# RACK32.net
KiCad netlist of a schematic drawn in EAGLE
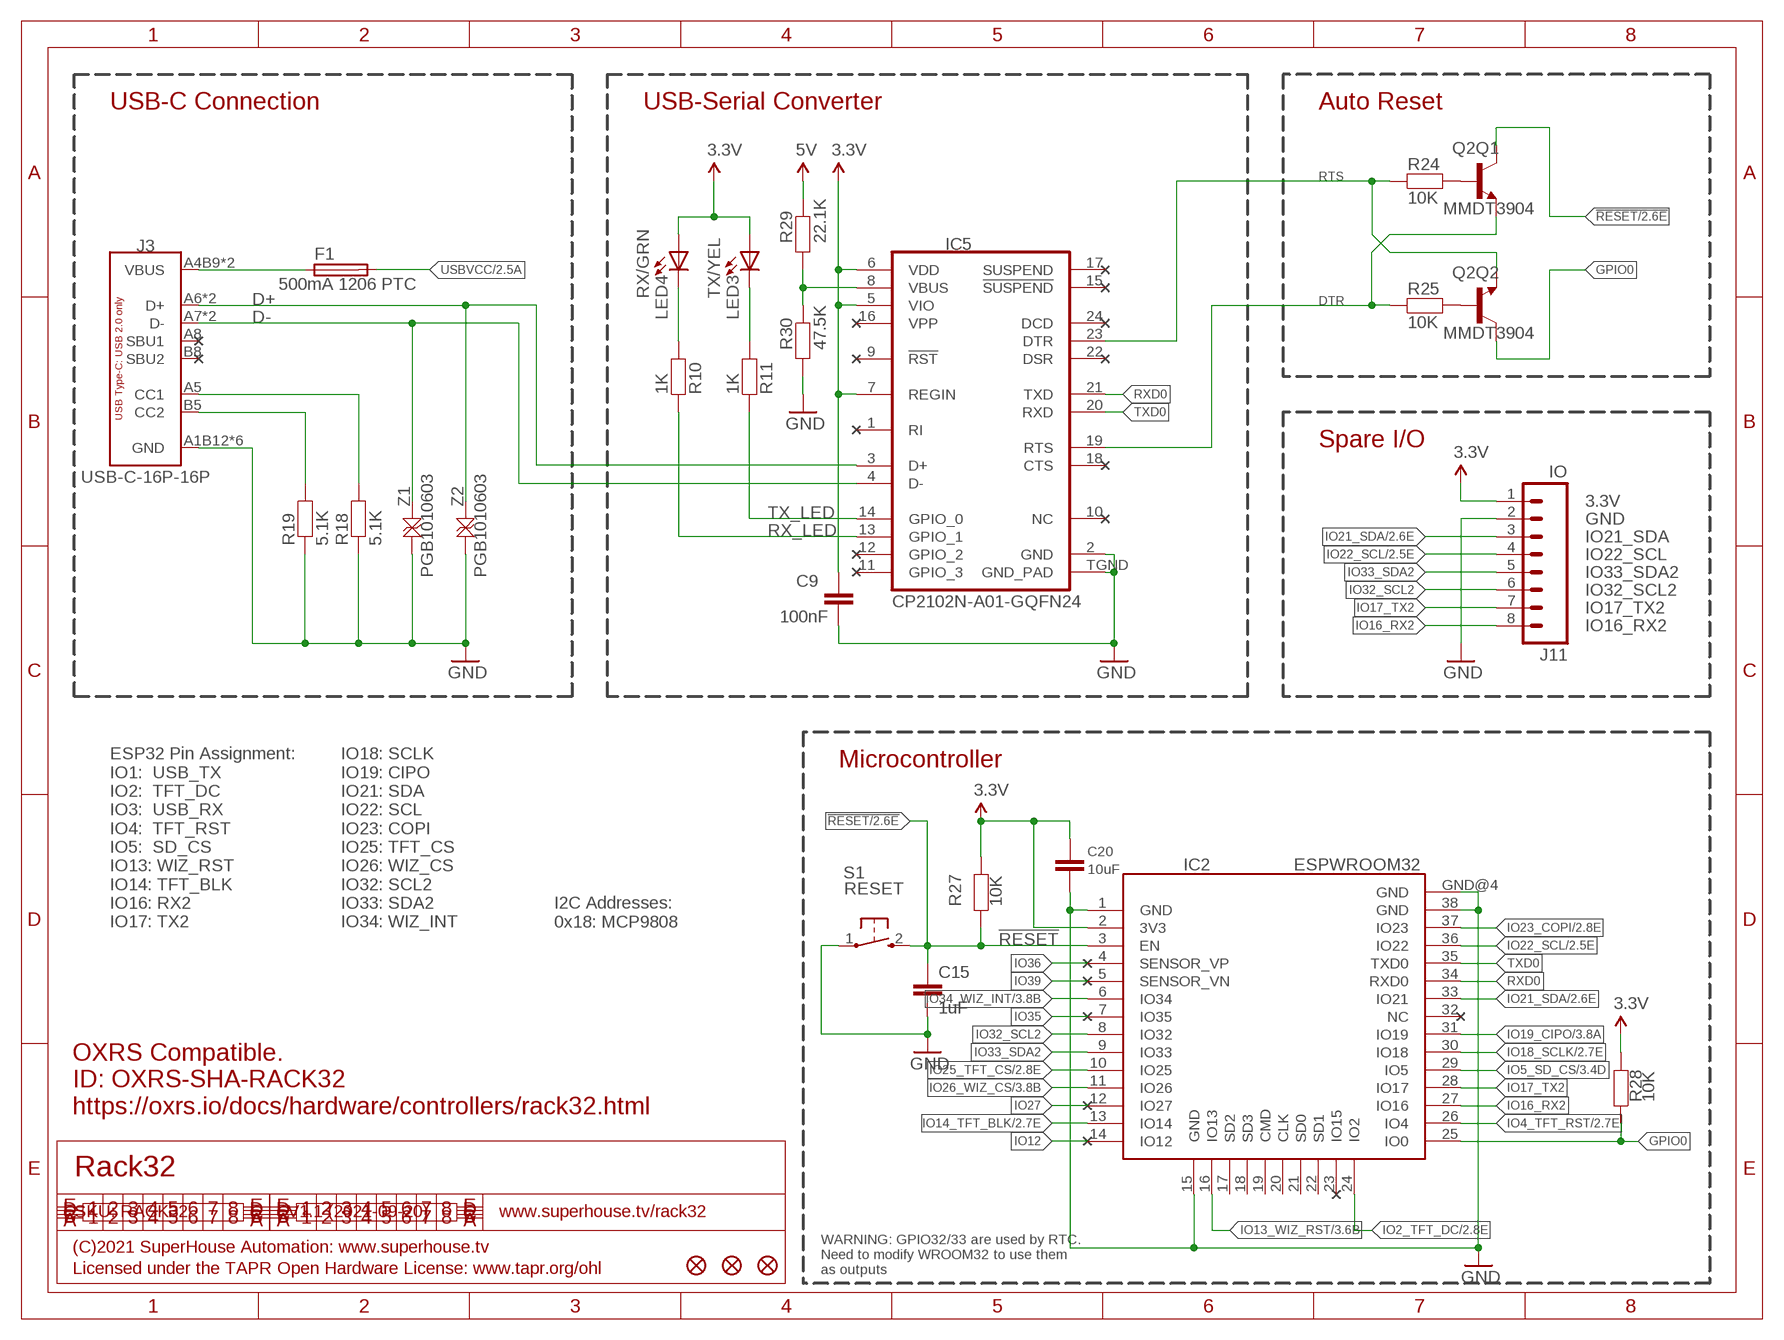
[diagram p0: schematic, sheet 1]
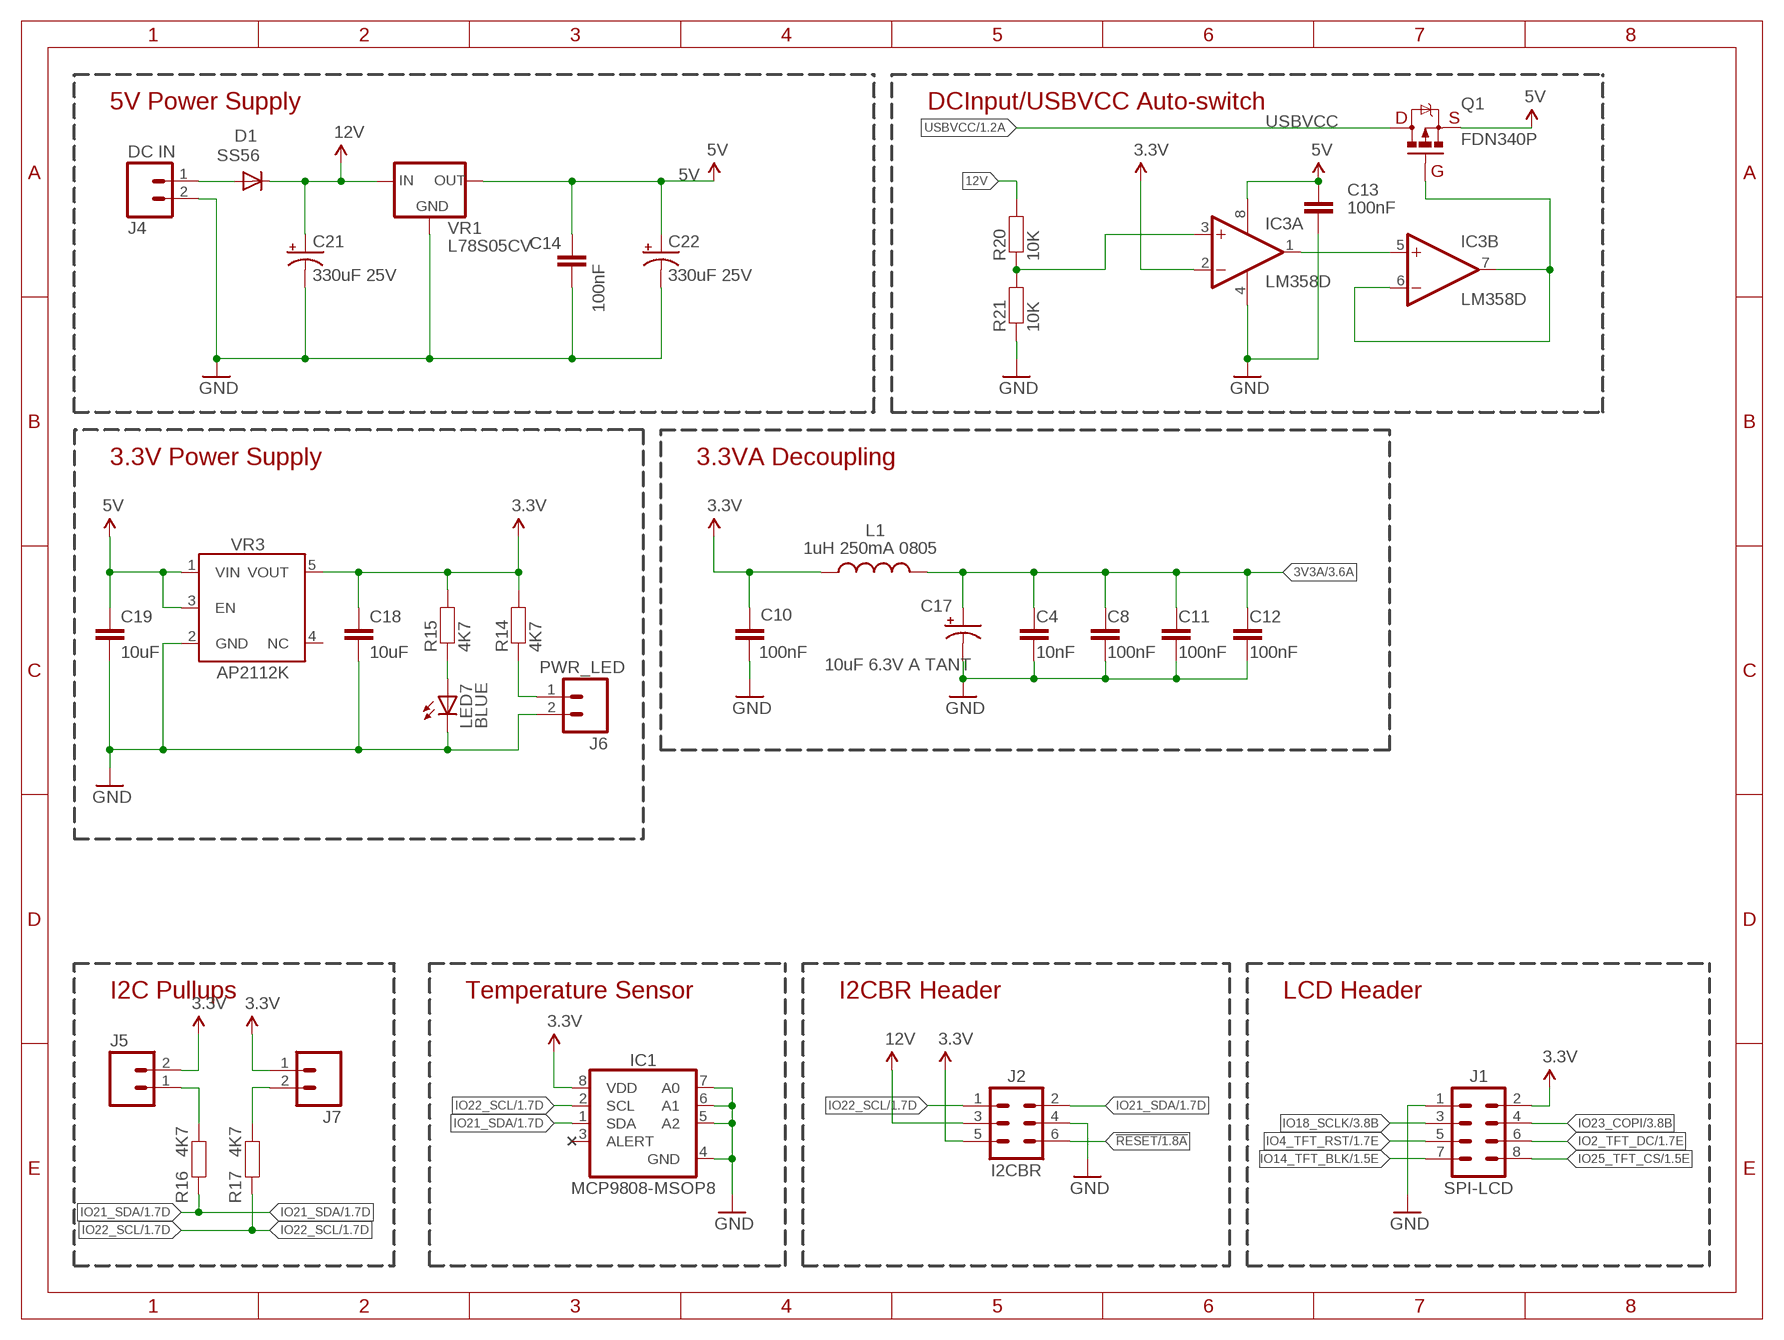
[diagram p1: schematic, sheet 2]
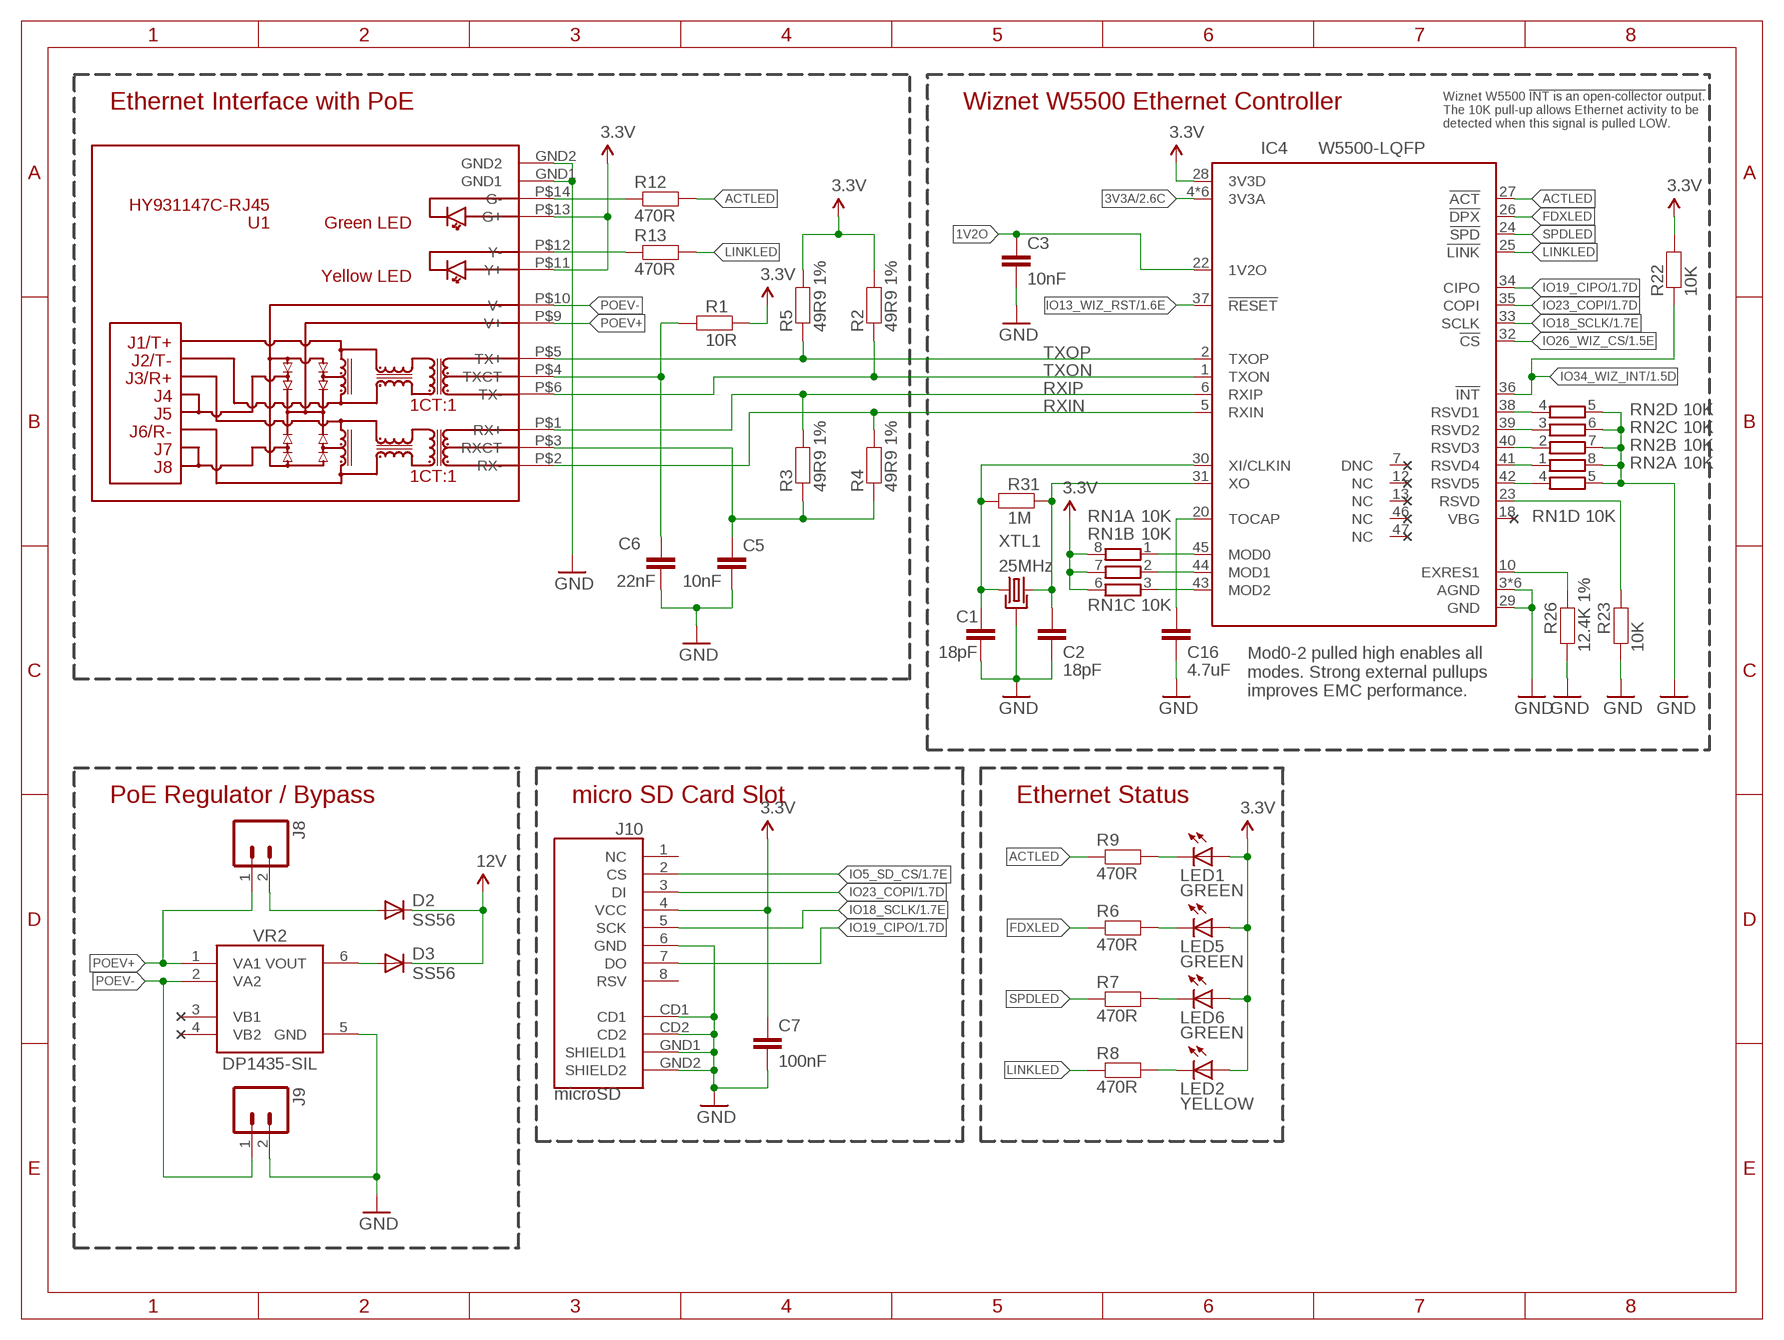
[diagram p2: schematic, sheet 3]

(export (version "E")
  (design (tool "Eeschema 10.0.6"))
  (components
    (comp (ref "C4")
      (value "10nF")
      (footprint "eagle-import:C0603")
      (libsource (lib "eagle-import") (part "CAP0603"))
    )
    (comp (ref "C8")
      (value "100nF")
      (footprint "eagle-import:C0603")
      (libsource (lib "eagle-import") (part "CAP0603"))
    )
    (comp (ref "C10")
      (value "100nF")
      (footprint "eagle-import:C0603")
      (libsource (lib "eagle-import") (part "CAP0603"))
    )
    (comp (ref "C11")
      (value "100nF")
      (footprint "eagle-import:C0603")
      (libsource (lib "eagle-import") (part "CAP0603"))
    )
    (comp (ref "C12")
      (value "100nF")
      (footprint "eagle-import:C0603")
      (libsource (lib "eagle-import") (part "CAP0603"))
    )
    (comp (ref "C13")
      (value "100nF")
      (footprint "eagle-import:C0603")
      (libsource (lib "eagle-import") (part "CAP0603"))
    )
    (comp (ref "C14")
      (value "100nF")
      (footprint "eagle-import:C0603")
      (libsource (lib "eagle-import") (part "CAP0603"))
    )
    (comp (ref "C17")
      (value "10uF 6.3V A TANT")
      (footprint "eagle-import:EIA3216")
      (libsource (lib "eagle-import") (part "CAP_POL1206"))
    )
    (comp (ref "C18")
      (value "10uF")
      (footprint "eagle-import:C0805")
      (libsource (lib "eagle-import") (part "CAP0805"))
    )
    (comp (ref "C19")
      (value "10uF")
      (footprint "eagle-import:C0805")
      (libsource (lib "eagle-import") (part "CAP0805"))
    )
    (comp (ref "C21")
      (value "330uF 25V")
      (footprint "eagle-import:PANASONIC_G")
      (libsource (lib "eagle-import") (part "CAP_POLG"))
    )
    (comp (ref "C22")
      (value "330uF 25V")
      (footprint "eagle-import:PANASONIC_G")
      (libsource (lib "eagle-import") (part "CAP_POLG"))
    )
    (comp (ref "D1")
      (value "SS56")
      (footprint "eagle-import:SMA-DIODE")
      (libsource (lib "eagle-import") (part "DIODESMA"))
    )
    (comp (ref "IC1")
      (value "MCP9808-MSOP8")
      (footprint "eagle-import:MSOP-8")
      (libsource (lib "eagle-import") (part "MCP9808-MSOP8"))
    )
    (comp (ref "IC3")
      (value "LM358D")
      (footprint "eagle-import:SO08")
      (libsource (lib "eagle-import") (part "LM358D"))
    )
    (comp (ref "J1")
      (value "SPI-LCD")
      (footprint "eagle-import:2X04-2.54-SHROUDED")
      (libsource (lib "eagle-import") (part "M02X4-SHROUD"))
    )
    (comp (ref "J2")
      (value "I2CBR")
      (footprint "eagle-import:2X3-2.54-SHROUDED")
      (libsource (lib "eagle-import") (part "M02X3-SHROUDED"))
    )
    (comp (ref "J4")
      (value "DC IN")
      (footprint "eagle-import:SCREWTERMINAL-3.81MM-HOR-2")
      (libsource (lib "eagle-import") (part "M02-SCREW-3.81MM-HOR"))
    )
    (comp (ref "J5")
      (value "M02-PIN-JUMP-Y")
      (footprint "eagle-import:1X02-P-JUMP-Y")
      (libsource (lib "eagle-import") (part "M02-PIN-JUMP-Y"))
    )
    (comp (ref "J6")
      (value "PWR_LED")
      (footprint "eagle-import:1X02-P")
      (libsource (lib "eagle-import") (part "M02-PIN"))
    )
    (comp (ref "J7")
      (value "M02-PIN-JUMP-Y")
      (footprint "eagle-import:1X02-P-JUMP-Y")
      (libsource (lib "eagle-import") (part "M02-PIN-JUMP-Y"))
    )
    (comp (ref "L1")
      (value "1uH 250mA 0805")
      (footprint "eagle-import:L2012C")
      (libsource (lib "eagle-import") (part "L-USL2012C"))
    )
    (comp (ref "LED7")
      (value "BLUE")
      (footprint "eagle-import:LED-0603")
      (libsource (lib "eagle-import") (part "LED0603"))
    )
    (comp (ref "Q1")
      (value "FDN340P")
      (footprint "eagle-import:SOT23-3")
      (libsource (lib "eagle-import") (part "MOSFET-PCHANNEL-SMT"))
    )
    (comp (ref "R14")
      (value "4K7")
      (footprint "eagle-import:R0603")
      (libsource (lib "eagle-import") (part "RESISTOR0603"))
    )
    (comp (ref "R15")
      (value "4K7")
      (footprint "eagle-import:R0603")
      (libsource (lib "eagle-import") (part "RESISTOR0603"))
    )
    (comp (ref "R16")
      (value "4K7")
      (footprint "eagle-import:R0603")
      (libsource (lib "eagle-import") (part "RESISTOR0603"))
    )
    (comp (ref "R17")
      (value "4K7")
      (footprint "eagle-import:R0603")
      (libsource (lib "eagle-import") (part "RESISTOR0603"))
    )
    (comp (ref "R20")
      (value "10K")
      (footprint "eagle-import:R0603")
      (libsource (lib "eagle-import") (part "RESISTOR0603"))
    )
    (comp (ref "R21")
      (value "10K")
      (footprint "eagle-import:R0603")
      (libsource (lib "eagle-import") (part "RESISTOR0603"))
    )
    (comp (ref "VR1")
      (value "L78S05CV")
      (footprint "eagle-import:TO220")
      (libsource (lib "eagle-import") (part "78XX-L78XX-FLAT"))
    )
    (comp (ref "VR3")
      (value "AP2112KSOT25")
      (footprint "eagle-import:SOT23-5")
      (libsource (lib "eagle-import") (part "AP2112KSOT25"))
    )
    (comp (ref "C1")
      (value "18pF")
      (footprint "eagle-import:C0603")
      (libsource (lib "eagle-import") (part "CAP0603"))
    )
    (comp (ref "C2")
      (value "18pF")
      (footprint "eagle-import:C0603")
      (libsource (lib "eagle-import") (part "CAP0603"))
    )
    (comp (ref "C3")
      (value "10nF")
      (footprint "eagle-import:C0603")
      (libsource (lib "eagle-import") (part "CAP0603"))
    )
    (comp (ref "C5")
      (value "10nF")
      (footprint "eagle-import:C0603")
      (libsource (lib "eagle-import") (part "CAP0603"))
    )
    (comp (ref "C6")
      (value "22nF")
      (footprint "eagle-import:C0603")
      (libsource (lib "eagle-import") (part "CAP0603"))
    )
    (comp (ref "C7")
      (value "100nF")
      (footprint "eagle-import:C0603")
      (libsource (lib "eagle-import") (part "CAP0603"))
    )
    (comp (ref "C16")
      (value "4.7uF")
      (footprint "eagle-import:C0603")
      (libsource (lib "eagle-import") (part "CAP0603"))
    )
    (comp (ref "D2")
      (value "SS56")
      (footprint "eagle-import:SMA-DIODE")
      (libsource (lib "eagle-import") (part "DIODESMA"))
    )
    (comp (ref "D3")
      (value "SS56")
      (footprint "eagle-import:SMA-DIODE")
      (libsource (lib "eagle-import") (part "DIODESMA"))
    )
    (comp (ref "IC4")
      (value "W5500-LQFP")
      (footprint "eagle-import:LQFP48")
      (libsource (lib "eagle-import") (part "W5500-LQFP"))
    )
    (comp (ref "J8")
      (value "M02-PIN-JUMP-Y")
      (footprint "eagle-import:1X02-P-JUMP-Y")
      (libsource (lib "eagle-import") (part "M02-PIN-JUMP-Y"))
    )
    (comp (ref "J9")
      (value "M02-PIN-JUMP-Y")
      (footprint "eagle-import:1X02-P-JUMP-Y")
      (libsource (lib "eagle-import") (part "M02-PIN-JUMP-Y"))
    )
    (comp (ref "J10")
      (value "microSD")
      (footprint "eagle-import:MICRO-SD-SOCKET-PP")
      (libsource (lib "eagle-import") (part "USD-SOCKETNEW"))
    )
    (comp (ref "LED1")
      (value "GREEN")
      (footprint "eagle-import:LED-0603")
      (libsource (lib "eagle-import") (part "LED0603"))
    )
    (comp (ref "LED2")
      (value "YELLOW")
      (footprint "eagle-import:LED-0603")
      (libsource (lib "eagle-import") (part "LED0603"))
    )
    (comp (ref "LED5")
      (value "GREEN")
      (footprint "eagle-import:LED-0603")
      (libsource (lib "eagle-import") (part "LED0603"))
    )
    (comp (ref "LED6")
      (value "GREEN")
      (footprint "eagle-import:LED-0603")
      (libsource (lib "eagle-import") (part "LED0603"))
    )
    (comp (ref "R1")
      (value "10R")
      (footprint "eagle-import:R0603")
      (libsource (lib "eagle-import") (part "RESISTOR0603"))
    )
    (comp (ref "R2")
      (value "49R9 1%")
      (footprint "eagle-import:R0603")
      (libsource (lib "eagle-import") (part "RESISTOR0603"))
    )
    (comp (ref "R3")
      (value "49R9 1%")
      (footprint "eagle-import:R0603")
      (libsource (lib "eagle-import") (part "RESISTOR0603"))
    )
    (comp (ref "R4")
      (value "49R9 1%")
      (footprint "eagle-import:R0603")
      (libsource (lib "eagle-import") (part "RESISTOR0603"))
    )
    (comp (ref "R5")
      (value "49R9 1%")
      (footprint "eagle-import:R0603")
      (libsource (lib "eagle-import") (part "RESISTOR0603"))
    )
    (comp (ref "R6")
      (value "470R")
      (footprint "eagle-import:R0603")
      (libsource (lib "eagle-import") (part "RESISTOR0603"))
    )
    (comp (ref "R7")
      (value "470R")
      (footprint "eagle-import:R0603")
      (libsource (lib "eagle-import") (part "RESISTOR0603"))
    )
    (comp (ref "R8")
      (value "470R")
      (footprint "eagle-import:R0603")
      (libsource (lib "eagle-import") (part "RESISTOR0603"))
    )
    (comp (ref "R9")
      (value "470R")
      (footprint "eagle-import:R0603")
      (libsource (lib "eagle-import") (part "RESISTOR0603"))
    )
    (comp (ref "R12")
      (value "470R")
      (footprint "eagle-import:R0603")
      (libsource (lib "eagle-import") (part "RESISTOR0603"))
    )
    (comp (ref "R13")
      (value "470R")
      (footprint "eagle-import:R0603")
      (libsource (lib "eagle-import") (part "RESISTOR0603"))
    )
    (comp (ref "R22")
      (value "10K")
      (footprint "eagle-import:R0603")
      (libsource (lib "eagle-import") (part "RESISTOR0603"))
    )
    (comp (ref "R23")
      (value "10K")
      (footprint "eagle-import:R0603")
      (libsource (lib "eagle-import") (part "RESISTOR0603"))
    )
    (comp (ref "R26")
      (value "12.4K 1%")
      (footprint "eagle-import:R0603")
      (libsource (lib "eagle-import") (part "RESISTOR0603"))
    )
    (comp (ref "R31")
      (value "1M")
      (footprint "eagle-import:R0603")
      (libsource (lib "eagle-import") (part "RESISTOR0603"))
    )
    (comp (ref "RN1")
      (value "10K")
      (footprint "eagle-import:CAY16")
      (libsource (lib "eagle-import") (part "4R-NCAY16"))
    )
    (comp (ref "RN2")
      (value "10K")
      (footprint "eagle-import:CAY16")
      (libsource (lib "eagle-import") (part "4R-NCAY16"))
    )
    (comp (ref "U1")
      (value "HY931147C-RJ45")
      (footprint "eagle-import:HY931147C")
      (libsource (lib "eagle-import") (part "HY931147C-RJ45"))
    )
    (comp (ref "VR2")
      (value "DP1435-SIL")
      (footprint "eagle-import:DP1435")
      (libsource (lib "eagle-import") (part "DP1435-SIL"))
    )
    (comp (ref "XTL1")
      (value "25MHz")
      (footprint "eagle-import:CRYSTAL-SMD-3X2")
      (libsource (lib "eagle-import") (part "CRYSTAL-GND3X2"))
    )
    (comp (ref "C9")
      (value "100nF")
      (footprint "eagle-import:C0603")
      (libsource (lib "eagle-import") (part "CAP0603"))
    )
    (comp (ref "C15")
      (value "1uF")
      (footprint "eagle-import:C0603")
      (libsource (lib "eagle-import") (part "CAP0603"))
    )
    (comp (ref "C20")
      (value "10uF")
      (footprint "eagle-import:C0805")
      (libsource (lib "eagle-import") (part "CAP0805"))
    )
    (comp (ref "F1")
      (value "500mA 1206 PTC")
      (footprint "eagle-import:1206")
      (libsource (lib "eagle-import") (part "PTC-1206"))
    )
    (comp (ref "FID1")
      (value "FIDUCIAL1X2.5")
      (footprint "eagle-import:FIDUCIAL-1X2.5")
      (libsource (lib "eagle-import") (part "FIDUCIAL1X2.5"))
    )
    (comp (ref "FID2")
      (value "FIDUCIAL1X2.5")
      (footprint "eagle-import:FIDUCIAL-1X2.5")
      (libsource (lib "eagle-import") (part "FIDUCIAL1X2.5"))
    )
    (comp (ref "FID3")
      (value "FIDUCIAL1X2.5")
      (footprint "eagle-import:FIDUCIAL-1X2.5")
      (libsource (lib "eagle-import") (part "FIDUCIAL1X2.5"))
    )
    (comp (ref "IC2")
      (value "ESPWROOM32")
      (footprint "eagle-import:ESPWROOM32")
      (libsource (lib "eagle-import") (part "ESPWROOM32"))
    )
    (comp (ref "IC5")
      (value "CP2102N-A01-GQFN24")
      (footprint "eagle-import:QFN-24")
      (libsource (lib "eagle-import") (part "CP2104"))
    )
    (comp (ref "J3")
      (value "USB-C-16P-16P")
      (footprint "eagle-import:USB-C-16P")
      (libsource (lib "eagle-import") (part "USB-C-16P-16P"))
    )
    (comp (ref "J11")
      (value "IO")
      (footprint "eagle-import:1X08")
      (libsource (lib "eagle-import") (part "M08-PLAIN"))
    )
    (comp (ref "LED3")
      (value "TX/YEL")
      (footprint "eagle-import:LED-0603")
      (libsource (lib "eagle-import") (part "LED0603"))
    )
    (comp (ref "LED4")
      (value "RX/GRN")
      (footprint "eagle-import:LED-0603")
      (libsource (lib "eagle-import") (part "LED0603"))
    )
    (comp (ref "Q2")
      (value "MMDT3904")
      (footprint "eagle-import:SOT-363")
      (libsource (lib "eagle-import") (part "TRANS_NPN_DUAL-MMDT3904"))
    )
    (comp (ref "R10")
      (value "1K")
      (footprint "eagle-import:R0603")
      (libsource (lib "eagle-import") (part "RESISTOR0603"))
    )
    (comp (ref "R11")
      (value "1K")
      (footprint "eagle-import:R0603")
      (libsource (lib "eagle-import") (part "RESISTOR0603"))
    )
    (comp (ref "R18")
      (value "5.1K")
      (footprint "eagle-import:R0603")
      (libsource (lib "eagle-import") (part "RESISTOR0603"))
    )
    (comp (ref "R19")
      (value "5.1K")
      (footprint "eagle-import:R0603")
      (libsource (lib "eagle-import") (part "RESISTOR0603"))
    )
    (comp (ref "R24")
      (value "10K")
      (footprint "eagle-import:R0603")
      (libsource (lib "eagle-import") (part "RESISTOR0603"))
    )
    (comp (ref "R25")
      (value "10K")
      (footprint "eagle-import:R0603")
      (libsource (lib "eagle-import") (part "RESISTOR0603"))
    )
    (comp (ref "R27")
      (value "10K")
      (footprint "eagle-import:R0603")
      (libsource (lib "eagle-import") (part "RESISTOR0603"))
    )
    (comp (ref "R28")
      (value "10K")
      (footprint "eagle-import:R0603")
      (libsource (lib "eagle-import") (part "RESISTOR0603"))
    )
    (comp (ref "R29")
      (value "22.1K")
      (footprint "eagle-import:R0603")
      (libsource (lib "eagle-import") (part "RESISTOR0603"))
    )
    (comp (ref "R30")
      (value "47.5K")
      (footprint "eagle-import:R0603")
      (libsource (lib "eagle-import") (part "RESISTOR0603"))
    )
    (comp (ref "S1")
      (value "RESET")
      (footprint "eagle-import:TACTILE_SMT_3X4X2")
      (libsource (lib "eagle-import") (part "TAC_SWITCH_2PINSMT"))
    )
    (comp (ref "Z1")
      (value "PGB1010603")
      (footprint "eagle-import:TVS0603")
      (libsource (lib "eagle-import") (part "TVS0603"))
    )
    (comp (ref "Z2")
      (value "PGB1010603")
      (footprint "eagle-import:TVS0603")
      (libsource (lib "eagle-import") (part "TVS0603"))
    )
  )
  (nets
    (net (code "1") (name "1V2O") (class "Default")
      (node (ref "C3") (pin "1") (pinfunction "1_1") (pintype "passive"))
      (node (ref "IC4") (pin "22") (pinfunction "1V2O_22") (pintype "passive"))
    )
    (net (code "2") (name "3.3V") (class "Default")
      (node (ref "C10") (pin "1") (pinfunction "1_1") (pintype "passive"))
      (node (ref "C18") (pin "1") (pinfunction "1_1") (pintype "passive"))
      (node (ref "C20") (pin "1") (pinfunction "1_1") (pintype "passive"))
      (node (ref "C7") (pin "1") (pinfunction "1_1") (pintype "passive"))
      (node (ref "C9") (pin "1") (pinfunction "1_1") (pintype "passive"))
      (node (ref "IC1") (pin "8") (pinfunction "VDD_8") (pintype "bidirectional"))
      (node (ref "IC2") (pin "2") (pinfunction "3V3_2") (pintype "power_in"))
      (node (ref "IC3") (pin "2") (pinfunction "-IN_2") (pintype "input"))
      (node (ref "IC4") (pin "28") (pinfunction "3V3D_28") (pintype "passive"))
      (node (ref "IC5") (pin "5") (pinfunction "VIO_5") (pintype "bidirectional"))
      (node (ref "IC5") (pin "6") (pinfunction "VDD_6") (pintype "power_in"))
      (node (ref "IC5") (pin "7") (pinfunction "REGIN_7") (pintype "power_in"))
      (node (ref "J1") (pin "2") (pinfunction "2_2") (pintype "passive"))
      (node (ref "J10") (pin "4") (pinfunction "VCC_4") (pintype "bidirectional"))
      (node (ref "J11") (pin "1") (pinfunction "1_1") (pintype "passive"))
      (node (ref "J2") (pin "5") (pinfunction "5_5") (pintype "passive"))
      (node (ref "J5") (pin "2") (pinfunction "2_2") (pintype "passive"))
      (node (ref "J7") (pin "1") (pinfunction "1_1") (pintype "passive"))
      (node (ref "L1") (pin "1") (pinfunction "1_1") (pintype "passive"))
      (node (ref "LED1") (pin "A") (pinfunction "A_A") (pintype "passive"))
      (node (ref "LED2") (pin "A") (pinfunction "A_A") (pintype "passive"))
      (node (ref "LED3") (pin "A") (pinfunction "A_A") (pintype "passive"))
      (node (ref "LED4") (pin "A") (pinfunction "A_A") (pintype "passive"))
      (node (ref "LED5") (pin "A") (pinfunction "A_A") (pintype "passive"))
      (node (ref "LED6") (pin "A") (pinfunction "A_A") (pintype "passive"))
      (node (ref "R1") (pin "1") (pinfunction "1_1") (pintype "passive"))
      (node (ref "R14") (pin "2") (pinfunction "2_2") (pintype "passive"))
      (node (ref "R15") (pin "2") (pinfunction "2_2") (pintype "passive"))
      (node (ref "R2") (pin "2") (pinfunction "2_2") (pintype "passive"))
      (node (ref "R22") (pin "2") (pinfunction "2_2") (pintype "passive"))
      (node (ref "R27") (pin "1") (pinfunction "1_1") (pintype "passive"))
      (node (ref "R28") (pin "1") (pinfunction "1_1") (pintype "passive"))
      (node (ref "R5") (pin "2") (pinfunction "2_2") (pintype "passive"))
      (node (ref "RN1") (pin "6") (pinfunction "2_6") (pintype "passive"))
      (node (ref "RN1") (pin "7") (pinfunction "2_7") (pintype "passive"))
      (node (ref "RN1") (pin "8") (pinfunction "2_8") (pintype "passive"))
      (node (ref "U1") (pin "P$11") (pinfunction "Y+_P$11") (pintype "bidirectional"))
      (node (ref "U1") (pin "P$13") (pinfunction "G+_P$13") (pintype "bidirectional"))
      (node (ref "VR3") (pin "5") (pinfunction "VOUT_5") (pintype "bidirectional"))
    )
    (net (code "3") (name "3V3A") (class "Default")
      (node (ref "C11") (pin "1") (pinfunction "1_1") (pintype "passive"))
      (node (ref "C12") (pin "1") (pinfunction "1_1") (pintype "passive"))
      (node (ref "C17") (pin "A") (pinfunction "+_A") (pintype "passive"))
      (node (ref "C4") (pin "1") (pinfunction "1_1") (pintype "passive"))
      (node (ref "C8") (pin "1") (pinfunction "1_1") (pintype "passive"))
      (node (ref "IC4") (pin "11") (pinfunction "3V3A_11") (pintype "passive"))
      (node (ref "IC4") (pin "15") (pinfunction "3V3A_15") (pintype "passive"))
      (node (ref "IC4") (pin "17") (pinfunction "3V3A_17") (pintype "passive"))
      (node (ref "IC4") (pin "21") (pinfunction "3V3A_21") (pintype "passive"))
      (node (ref "IC4") (pin "4") (pinfunction "3V3A_4") (pintype "passive"))
      (node (ref "IC4") (pin "8") (pinfunction "3V3A_8") (pintype "passive"))
      (node (ref "L1") (pin "2") (pinfunction "2_2") (pintype "passive"))
    )
    (net (code "4") (name "5V") (class "Default")
      (node (ref "C13") (pin "1") (pinfunction "1_1") (pintype "passive"))
      (node (ref "C14") (pin "1") (pinfunction "1_1") (pintype "passive"))
      (node (ref "C19") (pin "1") (pinfunction "1_1") (pintype "passive"))
      (node (ref "C22") (pin "+") (pinfunction "+_+") (pintype "passive"))
      (node (ref "IC3") (pin "8") (pinfunction "V+_8") (pintype "power_in"))
      (node (ref "Q1") (pin "2") (pinfunction "S_2") (pintype "passive"))
      (node (ref "R29") (pin "2") (pinfunction "2_2") (pintype "passive"))
      (node (ref "VR1") (pin "3") (pinfunction "OUT_3") (pintype "output"))
      (node (ref "VR3") (pin "1") (pinfunction "VIN_1") (pintype "bidirectional"))
      (node (ref "VR3") (pin "3") (pinfunction "EN_3") (pintype "bidirectional"))
    )
    (net (code "5") (name "12V") (class "Default")
      (node (ref "C21") (pin "+") (pinfunction "+_+") (pintype "passive"))
      (node (ref "D1") (pin "C") (pinfunction "C_C") (pintype "passive"))
      (node (ref "D2") (pin "C") (pinfunction "C_C") (pintype "passive"))
      (node (ref "D3") (pin "C") (pinfunction "C_C") (pintype "passive"))
      (node (ref "J2") (pin "3") (pinfunction "3_3") (pintype "passive"))
      (node (ref "R20") (pin "2") (pinfunction "2_2") (pintype "passive"))
      (node (ref "VR1") (pin "1") (pinfunction "IN_1") (pintype "input"))
    )
    (net (code "6") (name "ACTLED") (class "Default")
      (node (ref "IC4") (pin "27") (pinfunction "~{ACT}_27") (pintype "passive"))
      (node (ref "R12") (pin "2") (pinfunction "2_2") (pintype "passive"))
      (node (ref "R9") (pin "1") (pinfunction "1_1") (pintype "passive"))
    )
    (net (code "7") (name "D+") (class "Default")
      (node (ref "IC5") (pin "3") (pinfunction "D+_3") (pintype "bidirectional"))
      (node (ref "J3") (pin "A6") (pinfunction "D+_A6") (pintype "bidirectional"))
      (node (ref "J3") (pin "B6") (pinfunction "D+_B6") (pintype "bidirectional"))
      (node (ref "Z2") (pin "2") (pinfunction "2_2") (pintype "passive"))
    )
    (net (code "8") (name "D-") (class "Default")
      (node (ref "IC5") (pin "4") (pinfunction "D-_4") (pintype "bidirectional"))
      (node (ref "J3") (pin "A7") (pinfunction "D-_A7") (pintype "bidirectional"))
      (node (ref "J3") (pin "B7") (pinfunction "D-_B7") (pintype "bidirectional"))
      (node (ref "Z1") (pin "2") (pinfunction "2_2") (pintype "passive"))
    )
    (net (code "9") (name "DTR") (class "Default")
      (node (ref "IC5") (pin "23") (pinfunction "DTR_23") (pintype "output"))
      (node (ref "Q2") (pin "1") (pinfunction "E_1") (pintype "passive"))
      (node (ref "R24") (pin "1") (pinfunction "1_1") (pintype "passive"))
    )
    (net (code "10") (name "FDXLED") (class "Default")
      (node (ref "IC4") (pin "26") (pinfunction "~{DPX}_26") (pintype "passive"))
      (node (ref "R6") (pin "1") (pinfunction "1_1") (pintype "passive"))
    )
    (net (code "11") (name "GND") (class "Default")
      (node (ref "C1") (pin "2") (pinfunction "2_2") (pintype "passive"))
      (node (ref "C10") (pin "2") (pinfunction "2_2") (pintype "passive"))
      (node (ref "C11") (pin "2") (pinfunction "2_2") (pintype "passive"))
      (node (ref "C12") (pin "2") (pinfunction "2_2") (pintype "passive"))
      (node (ref "C13") (pin "2") (pinfunction "2_2") (pintype "passive"))
      (node (ref "C14") (pin "2") (pinfunction "2_2") (pintype "passive"))
      (node (ref "C15") (pin "2") (pinfunction "2_2") (pintype "passive"))
      (node (ref "C16") (pin "2") (pinfunction "2_2") (pintype "passive"))
      (node (ref "C17") (pin "C") (pinfunction "-_C") (pintype "passive"))
      (node (ref "C18") (pin "2") (pinfunction "2_2") (pintype "passive"))
      (node (ref "C19") (pin "2") (pinfunction "2_2") (pintype "passive"))
      (node (ref "C2") (pin "2") (pinfunction "2_2") (pintype "passive"))
      (node (ref "C20") (pin "2") (pinfunction "2_2") (pintype "passive"))
      (node (ref "C21") (pin "-") (pinfunction "-_-") (pintype "passive"))
      (node (ref "C22") (pin "-") (pinfunction "-_-") (pintype "passive"))
      (node (ref "C3") (pin "2") (pinfunction "2_2") (pintype "passive"))
      (node (ref "C4") (pin "2") (pinfunction "2_2") (pintype "passive"))
      (node (ref "C5") (pin "2") (pinfunction "2_2") (pintype "passive"))
      (node (ref "C6") (pin "2") (pinfunction "2_2") (pintype "passive"))
      (node (ref "C7") (pin "2") (pinfunction "2_2") (pintype "passive"))
      (node (ref "C8") (pin "2") (pinfunction "2_2") (pintype "passive"))
      (node (ref "C9") (pin "2") (pinfunction "2_2") (pintype "passive"))
      (node (ref "IC1") (pin "4") (pinfunction "GND_4") (pintype "bidirectional"))
      (node (ref "IC1") (pin "5") (pinfunction "A2_5") (pintype "bidirectional"))
      (node (ref "IC1") (pin "6") (pinfunction "A1_6") (pintype "bidirectional"))
      (node (ref "IC1") (pin "7") (pinfunction "A0_7") (pintype "bidirectional"))
      (node (ref "IC2") (pin "1") (pinfunction "GND_1") (pintype "power_in"))
      (node (ref "IC2") (pin "15") (pinfunction "GND_15") (pintype "power_in"))
      (node (ref "IC2") (pin "38") (pinfunction "GND_38") (pintype "power_in"))
      (node (ref "IC2") (pin "GND@4") (pinfunction "GND_GND@4") (pintype "power_in"))
      (node (ref "IC3") (pin "4") (pinfunction "V-_4") (pintype "power_in"))
      (node (ref "IC4") (pin "14") (pinfunction "AGND_14") (pintype "passive"))
      (node (ref "IC4") (pin "16") (pinfunction "AGND_16") (pintype "passive"))
      (node (ref "IC4") (pin "19") (pinfunction "AGND_19") (pintype "passive"))
      (node (ref "IC4") (pin "29") (pinfunction "GND_29") (pintype "passive"))
      (node (ref "IC4") (pin "3") (pinfunction "AGND_3") (pintype "passive"))
      (node (ref "IC4") (pin "48") (pinfunction "AGND_48") (pintype "passive"))
      (node (ref "IC4") (pin "9") (pinfunction "AGND_9") (pintype "passive"))
      (node (ref "IC5") (pin "2") (pinfunction "GND_2") (pintype "power_in"))
      (node (ref "IC5") (pin "TGND") (pinfunction "GND_PAD_TGND") (pintype "power_in"))
      (node (ref "J1") (pin "1") (pinfunction "1_1") (pintype "passive"))
      (node (ref "J10") (pin "6") (pinfunction "GND_6") (pintype "bidirectional"))
      (node (ref "J10") (pin "CD1") (pinfunction "CD1_CD1") (pintype "bidirectional"))
      (node (ref "J10") (pin "CD2") (pinfunction "CD2_CD2") (pintype "bidirectional"))
      (node (ref "J10") (pin "GND1") (pinfunction "SHIELD1_GND1") (pintype "bidirectional"))
      (node (ref "J10") (pin "GND2") (pinfunction "SHIELD2_GND2") (pintype "bidirectional"))
      (node (ref "J11") (pin "2") (pinfunction "2_2") (pintype "passive"))
      (node (ref "J2") (pin "4") (pinfunction "4_4") (pintype "passive"))
      (node (ref "J3") (pin "A12B1") (pinfunction "GND_A12B1") (pintype "power_in"))
      (node (ref "J3") (pin "A1B12") (pinfunction "GND_A1B12") (pintype "power_in"))
      (node (ref "J3") (pin "FIX1") (pinfunction "GND_FIX1") (pintype "power_in"))
      (node (ref "J3") (pin "FIX2") (pinfunction "GND_FIX2") (pintype "power_in"))
      (node (ref "J3") (pin "FIX3") (pinfunction "GND_FIX3") (pintype "power_in"))
      (node (ref "J3") (pin "FIX4") (pinfunction "GND_FIX4") (pintype "power_in"))
      (node (ref "J4") (pin "2") (pinfunction "2_2") (pintype "passive"))
      (node (ref "J6") (pin "2") (pinfunction "2_2") (pintype "passive"))
      (node (ref "J9") (pin "2") (pinfunction "2_2") (pintype "passive"))
      (node (ref "LED7") (pin "C") (pinfunction "C_C") (pintype "passive"))
      (node (ref "R18") (pin "1") (pinfunction "1_1") (pintype "passive"))
      (node (ref "R19") (pin "1") (pinfunction "1_1") (pintype "passive"))
      (node (ref "R21") (pin "1") (pinfunction "1_1") (pintype "passive"))
      (node (ref "R23") (pin "2") (pinfunction "2_2") (pintype "passive"))
      (node (ref "R26") (pin "2") (pinfunction "2_2") (pintype "passive"))
      (node (ref "R30") (pin "1") (pinfunction "1_1") (pintype "passive"))
      (node (ref "RN1") (pin "5") (pinfunction "2_5") (pintype "passive"))
      (node (ref "RN2") (pin "5") (pinfunction "2_5") (pintype "passive"))
      (node (ref "RN2") (pin "6") (pinfunction "2_6") (pintype "passive"))
      (node (ref "RN2") (pin "7") (pinfunction "2_7") (pintype "passive"))
      (node (ref "RN2") (pin "8") (pinfunction "2_8") (pintype "passive"))
      (node (ref "S1") (pin "1") (pinfunction "P_1") (pintype "passive"))
      (node (ref "U1") (pin "GND1") (pinfunction "GND1_GND1") (pintype "bidirectional"))
      (node (ref "U1") (pin "GND2") (pinfunction "GND2_GND2") (pintype "bidirectional"))
      (node (ref "VR1") (pin "2") (pinfunction "GND_2") (pintype "input"))
      (node (ref "VR1") (pin "HEATSINK") (pinfunction "GND_HEATSINK") (pintype "input"))
      (node (ref "VR1") (pin "TAB") (pinfunction "GND_TAB") (pintype "input"))
      (node (ref "VR2") (pin "5") (pinfunction "GND_5") (pintype "bidirectional"))
      (node (ref "VR3") (pin "2") (pinfunction "GND_2") (pintype "bidirectional"))
      (node (ref "XTL1") (pin "2") (pinfunction "GND_2") (pintype "bidirectional"))
      (node (ref "XTL1") (pin "4") (pinfunction "GND_4") (pintype "bidirectional"))
      (node (ref "Z1") (pin "1") (pinfunction "1_1") (pintype "passive"))
      (node (ref "Z2") (pin "1") (pinfunction "1_1") (pintype "passive"))
    )
    (net (code "12") (name "GPIO0") (class "Default")
      (node (ref "IC2") (pin "25") (pinfunction "IO0_25") (pintype "bidirectional"))
      (node (ref "Q2") (pin "6") (pinfunction "C_6") (pintype "passive"))
      (node (ref "R28") (pin "2") (pinfunction "2_2") (pintype "passive"))
    )
    (net (code "13") (name "IO2_TFT_DC") (class "Default")
      (node (ref "IC2") (pin "24") (pinfunction "IO2_24") (pintype "bidirectional"))
      (node (ref "J1") (pin "6") (pinfunction "6_6") (pintype "passive"))
    )
    (net (code "14") (name "IO4_TFT_RST") (class "Default")
      (node (ref "IC2") (pin "26") (pinfunction "IO4_26") (pintype "bidirectional"))
      (node (ref "J1") (pin "5") (pinfunction "5_5") (pintype "passive"))
    )
    (net (code "15") (name "IO5_SD_CS") (class "Default")
      (node (ref "IC2") (pin "29") (pinfunction "IO5_29") (pintype "bidirectional"))
      (node (ref "J10") (pin "2") (pinfunction "CS_2") (pintype "bidirectional"))
    )
    (net (code "16") (name "IO12") (class "Default")
      (node (ref "IC2") (pin "14") (pinfunction "IO12_14") (pintype "bidirectional"))
    )
    (net (code "17") (name "IO13_WIZ_RST") (class "Default")
      (node (ref "IC2") (pin "16") (pinfunction "IO13_16") (pintype "bidirectional"))
      (node (ref "IC4") (pin "37") (pinfunction "~{RESET}_37") (pintype "passive"))
    )
    (net (code "18") (name "IO14_TFT_BLK") (class "Default")
      (node (ref "IC2") (pin "13") (pinfunction "IO14_13") (pintype "bidirectional"))
      (node (ref "J1") (pin "7") (pinfunction "7_7") (pintype "passive"))
    )
    (net (code "19") (name "IO16_RX2") (class "Default")
      (node (ref "IC2") (pin "27") (pinfunction "IO16_27") (pintype "bidirectional"))
      (node (ref "J11") (pin "8") (pinfunction "8_8") (pintype "passive"))
    )
    (net (code "20") (name "IO17_TX2") (class "Default")
      (node (ref "IC2") (pin "28") (pinfunction "IO17_28") (pintype "bidirectional"))
      (node (ref "J11") (pin "7") (pinfunction "7_7") (pintype "passive"))
    )
    (net (code "21") (name "IO18_SCLK") (class "Default")
      (node (ref "IC2") (pin "30") (pinfunction "IO18_30") (pintype "bidirectional"))
      (node (ref "IC4") (pin "33") (pinfunction "SCLK_33") (pintype "passive"))
      (node (ref "J1") (pin "3") (pinfunction "3_3") (pintype "passive"))
      (node (ref "J10") (pin "5") (pinfunction "SCK_5") (pintype "bidirectional"))
    )
    (net (code "22") (name "IO19_CIPO") (class "Default")
      (node (ref "IC2") (pin "31") (pinfunction "IO19_31") (pintype "bidirectional"))
      (node (ref "IC4") (pin "34") (pinfunction "CIPO_34") (pintype "passive"))
      (node (ref "J10") (pin "7") (pinfunction "DO_7") (pintype "bidirectional"))
    )
    (net (code "23") (name "IO21_SDA") (class "Default")
      (node (ref "IC1") (pin "1") (pinfunction "SDA_1") (pintype "bidirectional"))
      (node (ref "IC2") (pin "33") (pinfunction "IO21_33") (pintype "bidirectional"))
      (node (ref "J11") (pin "3") (pinfunction "3_3") (pintype "passive"))
      (node (ref "J2") (pin "2") (pinfunction "2_2") (pintype "passive"))
      (node (ref "R16") (pin "2") (pinfunction "2_2") (pintype "passive"))
    )
    (net (code "24") (name "IO22_SCL") (class "Default")
      (node (ref "IC1") (pin "2") (pinfunction "SCL_2") (pintype "bidirectional"))
      (node (ref "IC2") (pin "36") (pinfunction "IO22_36") (pintype "bidirectional"))
      (node (ref "J11") (pin "4") (pinfunction "4_4") (pintype "passive"))
      (node (ref "J2") (pin "1") (pinfunction "1_1") (pintype "passive"))
      (node (ref "R17") (pin "2") (pinfunction "2_2") (pintype "passive"))
    )
    (net (code "25") (name "IO23_COPI") (class "Default")
      (node (ref "IC2") (pin "37") (pinfunction "IO23_37") (pintype "bidirectional"))
      (node (ref "IC4") (pin "35") (pinfunction "COPI_35") (pintype "passive"))
      (node (ref "J1") (pin "4") (pinfunction "4_4") (pintype "passive"))
      (node (ref "J10") (pin "3") (pinfunction "DI_3") (pintype "bidirectional"))
    )
    (net (code "26") (name "IO25_TFT_CS") (class "Default")
      (node (ref "IC2") (pin "10") (pinfunction "IO25_10") (pintype "bidirectional"))
      (node (ref "J1") (pin "8") (pinfunction "8_8") (pintype "passive"))
    )
    (net (code "27") (name "IO26_WIZ_CS") (class "Default")
      (node (ref "IC2") (pin "11") (pinfunction "IO26_11") (pintype "bidirectional"))
      (node (ref "IC4") (pin "32") (pinfunction "~{CS}_32") (pintype "passive"))
    )
    (net (code "28") (name "IO27") (class "Default")
      (node (ref "IC2") (pin "12") (pinfunction "IO27_12") (pintype "bidirectional"))
    )
    (net (code "29") (name "IO32_SCL2") (class "Default")
      (node (ref "IC2") (pin "8") (pinfunction "IO32_8") (pintype "bidirectional"))
      (node (ref "J11") (pin "6") (pinfunction "6_6") (pintype "passive"))
    )
    (net (code "30") (name "IO33_SDA2") (class "Default")
      (node (ref "IC2") (pin "9") (pinfunction "IO33_9") (pintype "bidirectional"))
      (node (ref "J11") (pin "5") (pinfunction "5_5") (pintype "passive"))
    )
    (net (code "31") (name "IO34_WIZ_INT") (class "Default")
      (node (ref "IC2") (pin "6") (pinfunction "IO34_6") (pintype "bidirectional"))
      (node (ref "IC4") (pin "36") (pinfunction "~{INT}_36") (pintype "passive"))
      (node (ref "R22") (pin "1") (pinfunction "1_1") (pintype "passive"))
    )
    (net (code "32") (name "IO35") (class "Default")
      (node (ref "IC2") (pin "7") (pinfunction "IO35_7") (pintype "bidirectional"))
    )
    (net (code "33") (name "IO36") (class "Default")
      (node (ref "IC2") (pin "4") (pinfunction "SENSOR_VP_4") (pintype "bidirectional"))
    )
    (net (code "34") (name "IO39") (class "Default")
      (node (ref "IC2") (pin "5") (pinfunction "SENSOR_VN_5") (pintype "bidirectional"))
    )
    (net (code "35") (name "LINKLED") (class "Default")
      (node (ref "IC4") (pin "25") (pinfunction "~{LINK}_25") (pintype "passive"))
      (node (ref "R13") (pin "2") (pinfunction "2_2") (pintype "passive"))
      (node (ref "R8") (pin "1") (pinfunction "1_1") (pintype "passive"))
    )
    (net (code "36") (name "Net-(D1-PadA)") (class "Default")
      (node (ref "D1") (pin "A") (pinfunction "A_A") (pintype "passive"))
      (node (ref "J4") (pin "1") (pinfunction "1_1") (pintype "passive"))
    )
    (net (code "37") (name "Net-(D2-PadA)") (class "Default")
      (node (ref "D2") (pin "A") (pinfunction "A_A") (pintype "passive"))
      (node (ref "J8") (pin "2") (pinfunction "2_2") (pintype "passive"))
    )
    (net (code "38") (name "Net-(F1-Pad1)") (class "Default")
      (node (ref "F1") (pin "1") (pinfunction "1_1") (pintype "passive"))
      (node (ref "J3") (pin "A4B9") (pinfunction "VBUS_A4B9") (pintype "power_in"))
      (node (ref "J3") (pin "A9B4") (pinfunction "VBUS_A9B4") (pintype "power_in"))
    )
    (net (code "39") (name "Net-(IC3A-+IN)") (class "Default")
      (node (ref "IC3") (pin "3") (pinfunction "+IN_3") (pintype "input"))
      (node (ref "R20") (pin "1") (pinfunction "1_1") (pintype "passive"))
      (node (ref "R21") (pin "2") (pinfunction "2_2") (pintype "passive"))
    )
    (net (code "40") (name "Net-(IC3A-OUT)") (class "Default")
      (node (ref "IC3") (pin "1") (pinfunction "OUT_1") (pintype "output"))
      (node (ref "IC3") (pin "5") (pinfunction "+IN_5") (pintype "input"))
    )
    (net (code "41") (name "Net-(IC3B--IN)") (class "Default")
      (node (ref "IC3") (pin "6") (pinfunction "-IN_6") (pintype "input"))
      (node (ref "IC3") (pin "7") (pinfunction "OUT_7") (pintype "output"))
      (node (ref "Q1") (pin "1") (pinfunction "G_1") (pintype "passive"))
    )
    (net (code "42") (name "Net-(IC4-EXRES1)") (class "Default")
      (node (ref "IC4") (pin "10") (pinfunction "EXRES1_10") (pintype "passive"))
      (node (ref "R26") (pin "1") (pinfunction "1_1") (pintype "passive"))
    )
    (net (code "43") (name "Net-(IC4-MOD0)") (class "Default")
      (node (ref "IC4") (pin "45") (pinfunction "MOD0_45") (pintype "passive"))
      (node (ref "RN1") (pin "1") (pinfunction "1_1") (pintype "passive"))
    )
    (net (code "44") (name "Net-(IC4-MOD1)") (class "Default")
      (node (ref "IC4") (pin "44") (pinfunction "MOD1_44") (pintype "passive"))
      (node (ref "RN1") (pin "2") (pinfunction "1_2") (pintype "passive"))
    )
    (net (code "45") (name "Net-(IC4-MOD2)") (class "Default")
      (node (ref "IC4") (pin "43") (pinfunction "MOD2_43") (pintype "passive"))
      (node (ref "RN1") (pin "3") (pinfunction "1_3") (pintype "passive"))
    )
    (net (code "46") (name "Net-(IC4-RSVD)") (class "Default")
      (node (ref "IC4") (pin "23") (pinfunction "RSVD_23") (pintype "passive"))
      (node (ref "R23") (pin "1") (pinfunction "1_1") (pintype "passive"))
    )
    (net (code "47") (name "Net-(IC4-RSVD1)") (class "Default")
      (node (ref "IC4") (pin "38") (pinfunction "RSVD1_38") (pintype "passive"))
      (node (ref "RN2") (pin "4") (pinfunction "1_4") (pintype "passive"))
    )
    (net (code "48") (name "Net-(IC4-RSVD2)") (class "Default")
      (node (ref "IC4") (pin "39") (pinfunction "RSVD2_39") (pintype "passive"))
      (node (ref "RN2") (pin "3") (pinfunction "1_3") (pintype "passive"))
    )
    (net (code "49") (name "Net-(IC4-RSVD3)") (class "Default")
      (node (ref "IC4") (pin "40") (pinfunction "RSVD3_40") (pintype "passive"))
      (node (ref "RN2") (pin "2") (pinfunction "1_2") (pintype "passive"))
    )
    (net (code "50") (name "Net-(IC4-RSVD4)") (class "Default")
      (node (ref "IC4") (pin "41") (pinfunction "RSVD4_41") (pintype "passive"))
      (node (ref "RN2") (pin "1") (pinfunction "1_1") (pintype "passive"))
    )
    (net (code "51") (name "Net-(IC4-RSVD5)") (class "Default")
      (node (ref "IC4") (pin "42") (pinfunction "RSVD5_42") (pintype "passive"))
      (node (ref "RN1") (pin "4") (pinfunction "1_4") (pintype "passive"))
    )
    (net (code "52") (name "Net-(IC4-TOCAP)") (class "Default")
      (node (ref "C16") (pin "1") (pinfunction "1_1") (pintype "passive"))
      (node (ref "IC4") (pin "20") (pinfunction "TOCAP_20") (pintype "passive"))
    )
    (net (code "53") (name "Net-(IC4-XI{slash}CLKIN)") (class "Default")
      (node (ref "C1") (pin "1") (pinfunction "1_1") (pintype "passive"))
      (node (ref "IC4") (pin "30") (pinfunction "XI/CLKIN_30") (pintype "passive"))
      (node (ref "R31") (pin "2") (pinfunction "2_2") (pintype "passive"))
      (node (ref "XTL1") (pin "1") (pinfunction "1_1") (pintype "passive"))
    )
    (net (code "54") (name "Net-(IC4-XO)") (class "Default")
      (node (ref "C2") (pin "1") (pinfunction "1_1") (pintype "passive"))
      (node (ref "IC4") (pin "31") (pinfunction "XO_31") (pintype "passive"))
      (node (ref "R31") (pin "1") (pinfunction "1_1") (pintype "passive"))
      (node (ref "XTL1") (pin "3") (pinfunction "2_3") (pintype "passive"))
    )
    (net (code "55") (name "Net-(IC5-VBUS)") (class "Default")
      (node (ref "IC5") (pin "8") (pinfunction "VBUS_8") (pintype "bidirectional"))
      (node (ref "R29") (pin "1") (pinfunction "1_1") (pintype "passive"))
      (node (ref "R30") (pin "2") (pinfunction "2_2") (pintype "passive"))
    )
    (net (code "56") (name "Net-(J3-CC1)") (class "Default")
      (node (ref "J3") (pin "A5") (pinfunction "CC1_A5") (pintype "bidirectional"))
      (node (ref "R18") (pin "2") (pinfunction "2_2") (pintype "passive"))
    )
    (net (code "57") (name "Net-(J3-CC2)") (class "Default")
      (node (ref "J3") (pin "B5") (pinfunction "CC2_B5") (pintype "bidirectional"))
      (node (ref "R19") (pin "2") (pinfunction "2_2") (pintype "passive"))
    )
    (net (code "58") (name "Net-(J5-Pad1)") (class "Default")
      (node (ref "J5") (pin "1") (pinfunction "1_1") (pintype "passive"))
      (node (ref "R16") (pin "1") (pinfunction "1_1") (pintype "passive"))
    )
    (net (code "59") (name "Net-(J6-Pad1)") (class "Default")
      (node (ref "J6") (pin "1") (pinfunction "1_1") (pintype "passive"))
      (node (ref "R14") (pin "1") (pinfunction "1_1") (pintype "passive"))
    )
    (net (code "60") (name "Net-(J7-Pad2)") (class "Default")
      (node (ref "J7") (pin "2") (pinfunction "2_2") (pintype "passive"))
      (node (ref "R17") (pin "1") (pinfunction "1_1") (pintype "passive"))
    )
    (net (code "61") (name "Net-(LED1-PadC)") (class "Default")
      (node (ref "LED1") (pin "C") (pinfunction "C_C") (pintype "passive"))
      (node (ref "R9") (pin "2") (pinfunction "2_2") (pintype "passive"))
    )
    (net (code "62") (name "Net-(LED2-PadC)") (class "Default")
      (node (ref "LED2") (pin "C") (pinfunction "C_C") (pintype "passive"))
      (node (ref "R8") (pin "2") (pinfunction "2_2") (pintype "passive"))
    )
    (net (code "63") (name "Net-(LED3-PadC)") (class "Default")
      (node (ref "LED3") (pin "C") (pinfunction "C_C") (pintype "passive"))
      (node (ref "R11") (pin "2") (pinfunction "2_2") (pintype "passive"))
    )
    (net (code "64") (name "Net-(LED4-PadC)") (class "Default")
      (node (ref "LED4") (pin "C") (pinfunction "C_C") (pintype "passive"))
      (node (ref "R10") (pin "2") (pinfunction "2_2") (pintype "passive"))
    )
    (net (code "65") (name "Net-(LED5-PadC)") (class "Default")
      (node (ref "LED5") (pin "C") (pinfunction "C_C") (pintype "passive"))
      (node (ref "R6") (pin "2") (pinfunction "2_2") (pintype "passive"))
    )
    (net (code "66") (name "Net-(LED6-PadC)") (class "Default")
      (node (ref "LED6") (pin "C") (pinfunction "C_C") (pintype "passive"))
      (node (ref "R7") (pin "2") (pinfunction "2_2") (pintype "passive"))
    )
    (net (code "67") (name "Net-(LED7-PadA)") (class "Default")
      (node (ref "LED7") (pin "A") (pinfunction "A_A") (pintype "passive"))
      (node (ref "R15") (pin "1") (pinfunction "1_1") (pintype "passive"))
    )
    (net (code "68") (name "Net-(Q2A-B)") (class "Default")
      (node (ref "Q2") (pin "5") (pinfunction "B_5") (pintype "passive"))
      (node (ref "R24") (pin "2") (pinfunction "2_2") (pintype "passive"))
    )
    (net (code "69") (name "Net-(Q2B-B)") (class "Default")
      (node (ref "Q2") (pin "2") (pinfunction "B_2") (pintype "passive"))
      (node (ref "R25") (pin "2") (pinfunction "2_2") (pintype "passive"))
    )
    (net (code "70") (name "Net-(U1-G-)") (class "Default")
      (node (ref "R12") (pin "1") (pinfunction "1_1") (pintype "passive"))
      (node (ref "U1") (pin "P$14") (pinfunction "G-_P$14") (pintype "bidirectional"))
    )
    (net (code "71") (name "Net-(U1-RXCT)") (class "Default")
      (node (ref "C5") (pin "1") (pinfunction "1_1") (pintype "passive"))
      (node (ref "R3") (pin "1") (pinfunction "1_1") (pintype "passive"))
      (node (ref "R4") (pin "1") (pinfunction "1_1") (pintype "passive"))
      (node (ref "U1") (pin "P$3") (pinfunction "RXCT_P$3") (pintype "bidirectional"))
    )
    (net (code "72") (name "Net-(U1-TXCT)") (class "Default")
      (node (ref "C6") (pin "1") (pinfunction "1_1") (pintype "passive"))
      (node (ref "R1") (pin "2") (pinfunction "2_2") (pintype "passive"))
      (node (ref "U1") (pin "P$4") (pinfunction "TXCT_P$4") (pintype "bidirectional"))
    )
    (net (code "73") (name "Net-(U1-Y-)") (class "Default")
      (node (ref "R13") (pin "1") (pinfunction "1_1") (pintype "passive"))
      (node (ref "U1") (pin "P$12") (pinfunction "Y-_P$12") (pintype "bidirectional"))
    )
    (net (code "74") (name "Net-(VR2-VOUT)") (class "Default")
      (node (ref "D3") (pin "A") (pinfunction "A_A") (pintype "passive"))
      (node (ref "VR2") (pin "6") (pinfunction "VOUT_6") (pintype "bidirectional"))
    )
    (net (code "75") (name "POEV+") (class "Default")
      (node (ref "J8") (pin "1") (pinfunction "1_1") (pintype "passive"))
      (node (ref "U1") (pin "P$9") (pinfunction "V+_P$9") (pintype "bidirectional"))
      (node (ref "VR2") (pin "1") (pinfunction "VA1_1") (pintype "power_in"))
    )
    (net (code "76") (name "POEV-") (class "Default")
      (node (ref "J9") (pin "1") (pinfunction "1_1") (pintype "passive"))
      (node (ref "U1") (pin "P$10") (pinfunction "V-_P$10") (pintype "bidirectional"))
      (node (ref "VR2") (pin "2") (pinfunction "VA2_2") (pintype "power_in"))
    )
    (net (code "77") (name "RTS") (class "Default")
      (node (ref "IC5") (pin "19") (pinfunction "RTS_19") (pintype "output"))
      (node (ref "Q2") (pin "4") (pinfunction "E_4") (pintype "passive"))
      (node (ref "R25") (pin "1") (pinfunction "1_1") (pintype "passive"))
    )
    (net (code "78") (name "RXD0") (class "Default")
      (node (ref "IC2") (pin "34") (pinfunction "RXD0_34") (pintype "bidirectional"))
      (node (ref "IC5") (pin "21") (pinfunction "TXD_21") (pintype "output"))
    )
    (net (code "79") (name "RXIN") (class "Default")
      (node (ref "IC4") (pin "5") (pinfunction "RXIN_5") (pintype "passive"))
      (node (ref "R4") (pin "2") (pinfunction "2_2") (pintype "passive"))
      (node (ref "U1") (pin "P$2") (pinfunction "RX-_P$2") (pintype "bidirectional"))
    )
    (net (code "80") (name "RXIP") (class "Default")
      (node (ref "IC4") (pin "6") (pinfunction "RXIP_6") (pintype "passive"))
      (node (ref "R3") (pin "2") (pinfunction "2_2") (pintype "passive"))
      (node (ref "U1") (pin "P$1") (pinfunction "RX+_P$1") (pintype "bidirectional"))
    )
    (net (code "81") (name "RX_LED") (class "Default")
      (node (ref "IC5") (pin "13") (pinfunction "GPIO_1_13") (pintype "bidirectional"))
      (node (ref "R10") (pin "1") (pinfunction "1_1") (pintype "passive"))
    )
    (net (code "82") (name "SPDLED") (class "Default")
      (node (ref "IC4") (pin "24") (pinfunction "~{SPD}_24") (pintype "passive"))
      (node (ref "R7") (pin "1") (pinfunction "1_1") (pintype "passive"))
    )
    (net (code "83") (name "TXD0") (class "Default")
      (node (ref "IC2") (pin "35") (pinfunction "TXD0_35") (pintype "bidirectional"))
      (node (ref "IC5") (pin "20") (pinfunction "RXD_20") (pintype "input"))
    )
    (net (code "84") (name "TXON") (class "Default")
      (node (ref "IC4") (pin "1") (pinfunction "TXON_1") (pintype "passive"))
      (node (ref "R2") (pin "1") (pinfunction "1_1") (pintype "passive"))
      (node (ref "U1") (pin "P$6") (pinfunction "TX-_P$6") (pintype "bidirectional"))
    )
    (net (code "85") (name "TXOP") (class "Default")
      (node (ref "IC4") (pin "2") (pinfunction "TXOP_2") (pintype "passive"))
      (node (ref "R5") (pin "1") (pinfunction "1_1") (pintype "passive"))
      (node (ref "U1") (pin "P$5") (pinfunction "TX+_P$5") (pintype "bidirectional"))
    )
    (net (code "86") (name "TX_LED") (class "Default")
      (node (ref "IC5") (pin "14") (pinfunction "GPIO_0_14") (pintype "bidirectional"))
      (node (ref "R11") (pin "1") (pinfunction "1_1") (pintype "passive"))
    )
    (net (code "87") (name "USBVCC") (class "Default")
      (node (ref "F1") (pin "2") (pinfunction "2_2") (pintype "passive"))
      (node (ref "Q1") (pin "3") (pinfunction "D_3") (pintype "passive"))
    )
    (net (code "88") (name "VB1") (class "Default")
      (node (ref "VR2") (pin "3") (pinfunction "VB1_3") (pintype "power_in"))
    )
    (net (code "89") (name "VB2") (class "Default")
      (node (ref "VR2") (pin "4") (pinfunction "VB2_4") (pintype "power_in"))
    )
    (net (code "90") (name "unconnected-(IC1-ALERT-Pad3)") (class "Default")
      (node (ref "IC1") (pin "3") (pinfunction "ALERT_3") (pintype "bidirectional"))
    )
    (net (code "91") (name "unconnected-(IC2-CLK-Pad20)") (class "Default")
      (node (ref "IC2") (pin "20") (pinfunction "CLK_20") (pintype "bidirectional"))
    )
    (net (code "92") (name "unconnected-(IC2-CMD-Pad19)") (class "Default")
      (node (ref "IC2") (pin "19") (pinfunction "CMD_19") (pintype "bidirectional"))
    )
    (net (code "93") (name "unconnected-(IC2-IO15-Pad23)") (class "Default")
      (node (ref "IC2") (pin "23") (pinfunction "IO15_23") (pintype "bidirectional"))
    )
    (net (code "94") (name "unconnected-(IC2-NC-Pad32)") (class "Default")
      (node (ref "IC2") (pin "32") (pinfunction "NC_32") (pintype "bidirectional"))
    )
    (net (code "95") (name "unconnected-(IC2-SD0-Pad21)") (class "Default")
      (node (ref "IC2") (pin "21") (pinfunction "SD0_21") (pintype "bidirectional"))
    )
    (net (code "96") (name "unconnected-(IC2-SD1-Pad22)") (class "Default")
      (node (ref "IC2") (pin "22") (pinfunction "SD1_22") (pintype "bidirectional"))
    )
    (net (code "97") (name "unconnected-(IC2-SD2-Pad17)") (class "Default")
      (node (ref "IC2") (pin "17") (pinfunction "SD2_17") (pintype "bidirectional"))
    )
    (net (code "98") (name "unconnected-(IC2-SD3-Pad18)") (class "Default")
      (node (ref "IC2") (pin "18") (pinfunction "SD3_18") (pintype "bidirectional"))
    )
    (net (code "99") (name "unconnected-(IC4-DNC-Pad7)") (class "Default")
      (node (ref "IC4") (pin "7") (pinfunction "DNC_7") (pintype "passive"))
    )
    (net (code "100") (name "unconnected-(IC4-NC-Pad12)") (class "Default")
      (node (ref "IC4") (pin "12") (pinfunction "NC_12") (pintype "passive"))
    )
    (net (code "101") (name "unconnected-(IC4-NC-Pad13)") (class "Default")
      (node (ref "IC4") (pin "13") (pinfunction "NC_13") (pintype "passive"))
    )
    (net (code "102") (name "unconnected-(IC4-NC-Pad46)") (class "Default")
      (node (ref "IC4") (pin "46") (pinfunction "NC_46") (pintype "passive"))
    )
    (net (code "103") (name "unconnected-(IC4-NC-Pad47)") (class "Default")
      (node (ref "IC4") (pin "47") (pinfunction "NC_47") (pintype "passive"))
    )
    (net (code "104") (name "unconnected-(IC4-VBG-Pad18)") (class "Default")
      (node (ref "IC4") (pin "18") (pinfunction "VBG_18") (pintype "passive"))
    )
    (net (code "105") (name "unconnected-(IC5-CTS-Pad18)") (class "Default")
      (node (ref "IC5") (pin "18") (pinfunction "CTS_18") (pintype "input"))
    )
    (net (code "106") (name "unconnected-(IC5-DCD-Pad24)") (class "Default")
      (node (ref "IC5") (pin "24") (pinfunction "DCD_24") (pintype "input"))
    )
    (net (code "107") (name "unconnected-(IC5-DSR-Pad22)") (class "Default")
      (node (ref "IC5") (pin "22") (pinfunction "DSR_22") (pintype "input"))
    )
    (net (code "108") (name "unconnected-(IC5-GPIO_2-Pad12)") (class "Default")
      (node (ref "IC5") (pin "12") (pinfunction "GPIO_2_12") (pintype "bidirectional"))
    )
    (net (code "109") (name "unconnected-(IC5-GPIO_3-Pad11)") (class "Default")
      (node (ref "IC5") (pin "11") (pinfunction "GPIO_3_11") (pintype "bidirectional"))
    )
    (net (code "110") (name "unconnected-(IC5-NC-Pad10)") (class "Default")
      (node (ref "IC5") (pin "10") (pinfunction "NC_10") (pintype "input"))
    )
    (net (code "111") (name "unconnected-(IC5-RI-Pad1)") (class "Default")
      (node (ref "IC5") (pin "1") (pinfunction "RI_1") (pintype "input"))
    )
    (net (code "112") (name "unconnected-(IC5-SUSPEND-Pad17)") (class "Default")
      (node (ref "IC5") (pin "17") (pinfunction "SUSPEND_17") (pintype "output"))
    )
    (net (code "113") (name "unconnected-(IC5-VPP-Pad16)") (class "Default")
      (node (ref "IC5") (pin "16") (pinfunction "VPP_16") (pintype "bidirectional"))
    )
    (net (code "114") (name "unconnected-(IC5-~{RST}-Pad9)") (class "Default")
      (node (ref "IC5") (pin "9") (pinfunction "~{RST}_9") (pintype "bidirectional"))
    )
    (net (code "115") (name "unconnected-(IC5-~{SUSPEND}-Pad15)") (class "Default")
      (node (ref "IC5") (pin "15") (pinfunction "~{SUSPEND}_15") (pintype "output"))
    )
    (net (code "116") (name "unconnected-(J3-SBU1-PadA8)") (class "Default")
      (node (ref "J3") (pin "A8") (pinfunction "SBU1_A8") (pintype "bidirectional"))
    )
    (net (code "117") (name "unconnected-(J3-SBU2-PadB8)") (class "Default")
      (node (ref "J3") (pin "B8") (pinfunction "SBU2_B8") (pintype "bidirectional"))
    )
    (net (code "118") (name "unconnected-(J10-NC-Pad1)") (class "Default")
      (node (ref "J10") (pin "1") (pinfunction "NC_1") (pintype "bidirectional"))
    )
    (net (code "119") (name "unconnected-(J10-RSV-Pad8)") (class "Default")
      (node (ref "J10") (pin "8") (pinfunction "RSV_8") (pintype "bidirectional"))
    )
    (net (code "120") (name "unconnected-(VR3-NC-Pad4)") (class "Default")
      (node (ref "VR3") (pin "4") (pinfunction "NC_4") (pintype "bidirectional"))
    )
    (net (code "121") (name "~{RESET}") (class "Default")
      (node (ref "C15") (pin "1") (pinfunction "1_1") (pintype "passive"))
      (node (ref "IC2") (pin "3") (pinfunction "EN_3") (pintype "bidirectional"))
      (node (ref "J2") (pin "6") (pinfunction "6_6") (pintype "passive"))
      (node (ref "Q2") (pin "3") (pinfunction "C_3") (pintype "passive"))
      (node (ref "R27") (pin "2") (pinfunction "2_2") (pintype "passive"))
      (node (ref "S1") (pin "2") (pinfunction "S_2") (pintype "passive"))
    )
  )
)
